# fridge-t10.net
KiCad netlist of a schematic drawn in EAGLE
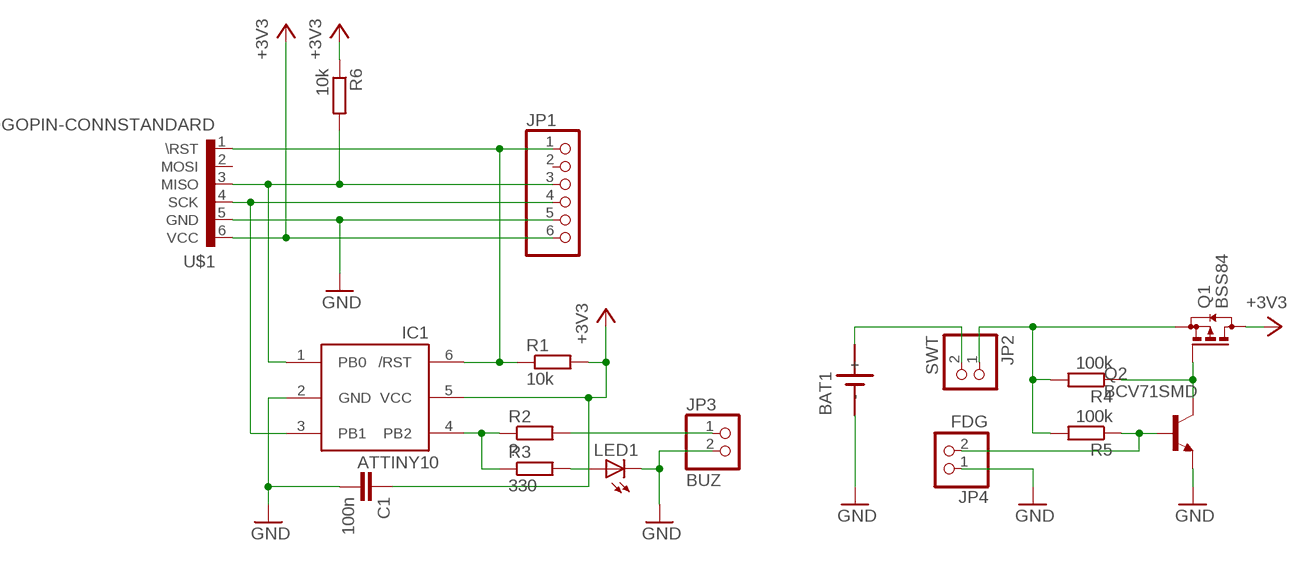
[diagram p0: schematic, sheet 1]

(export (version "E")
  (design (tool "Eeschema 10.0.6"))
  (components
    (comp (ref "BAT1")
      (value "SN2032")
      (footprint "eagle-import:SN2032")
      (libsource (lib "eagle-import") (part "SN2032"))
    )
    (comp (ref "C1")
      (value "100n")
      (footprint "eagle-import:C0805K")
      (libsource (lib "eagle-import") (part "C-EUC0805K"))
    )
    (comp (ref "IC1")
      (value "ATTINY10")
      (footprint "eagle-import:SOT23-6")
      (libsource (lib "eagle-import") (part "ATTINY10"))
    )
    (comp (ref "JP1")
      (value "PINHD-1X6")
      (footprint "eagle-import:1X06")
      (libsource (lib "eagle-import") (part "PINHD-1X6"))
    )
    (comp (ref "JP2")
      (value "SWT")
      (footprint "eagle-import:1X02")
      (libsource (lib "eagle-import") (part "PINHD-1X2"))
    )
    (comp (ref "JP3")
      (value "BUZ")
      (footprint "eagle-import:1X02")
      (libsource (lib "eagle-import") (part "PINHD-1X2"))
    )
    (comp (ref "JP4")
      (value "FDG")
      (footprint "eagle-import:1X02")
      (libsource (lib "eagle-import") (part "PINHD-1X2"))
    )
    (comp (ref "LED1")
      (value "LEDCHIPLED_0805")
      (footprint "eagle-import:CHIPLED_0805")
      (libsource (lib "eagle-import") (part "LEDCHIPLED_0805"))
    )
    (comp (ref "Q1")
      (value "BSS84")
      (footprint "eagle-import:SOT23")
      (libsource (lib "eagle-import") (part "BSS84"))
    )
    (comp (ref "Q2")
      (value "BCV71SMD")
      (footprint "eagle-import:SOT23-BEC")
      (libsource (lib "eagle-import") (part "BCV71SMD"))
    )
    (comp (ref "R1")
      (value "10k")
      (footprint "eagle-import:R0805")
      (libsource (lib "eagle-import") (part "R-EU_R0805"))
    )
    (comp (ref "R2")
      (value "?")
      (footprint "eagle-import:R0805")
      (libsource (lib "eagle-import") (part "R-EU_R0805"))
    )
    (comp (ref "R3")
      (value "330")
      (footprint "eagle-import:R0805")
      (libsource (lib "eagle-import") (part "R-EU_R0805"))
    )
    (comp (ref "R4")
      (value "100k")
      (footprint "eagle-import:R0805")
      (libsource (lib "eagle-import") (part "R-EU_R0805"))
    )
    (comp (ref "R5")
      (value "100k")
      (footprint "eagle-import:R0805")
      (libsource (lib "eagle-import") (part "R-EU_R0805"))
    )
    (comp (ref "R6")
      (value "10k")
      (footprint "eagle-import:R0805")
      (libsource (lib "eagle-import") (part "R-EU_R0805"))
    )
    (comp (ref "U$1")
      (value "POGOPIN-CONNSTANDARD")
      (footprint "eagle-import:POGOPROG-CONN")
      (libsource (lib "eagle-import") (part "POGOPIN-CONNSTANDARD"))
    )
  )
  (nets
    (net (code "1") (name "+3V3") (class "Default")
      (node (ref "C1") (pin "1") (pinfunction "1_1") (pintype "passive"))
      (node (ref "IC1") (pin "5") (pinfunction "VCC_5") (pintype "power_in"))
      (node (ref "JP1") (pin "6") (pinfunction "6_6") (pintype "passive"))
      (node (ref "Q1") (pin "3") (pinfunction "D_3") (pintype "passive"))
      (node (ref "R1") (pin "2") (pinfunction "2_2") (pintype "passive"))
      (node (ref "R6") (pin "1") (pinfunction "1_1") (pintype "passive"))
      (node (ref "U$1") (pin "6") (pinfunction "VCC_6") (pintype "bidirectional"))
    )
    (net (code "2") (name "GND") (class "Default")
      (node (ref "BAT1") (pin "-") (pinfunction "-_-") (pintype "passive"))
      (node (ref "C1") (pin "2") (pinfunction "2_2") (pintype "passive"))
      (node (ref "IC1") (pin "2") (pinfunction "GND_2") (pintype "power_in"))
      (node (ref "JP1") (pin "5") (pinfunction "5_5") (pintype "passive"))
      (node (ref "JP3") (pin "2") (pinfunction "2_2") (pintype "passive"))
      (node (ref "JP4") (pin "1") (pinfunction "1_1") (pintype "passive"))
      (node (ref "LED1") (pin "C") (pinfunction "C_C") (pintype "passive"))
      (node (ref "Q2") (pin "E") (pinfunction "E_E") (pintype "passive"))
      (node (ref "U$1") (pin "5") (pinfunction "GND_5") (pintype "bidirectional"))
    )
    (net (code "3") (name "Net-(BAT1-Pad+)") (class "Default")
      (node (ref "BAT1") (pin "+") (pinfunction "+_+") (pintype "passive"))
      (node (ref "JP2") (pin "2") (pinfunction "2_2") (pintype "passive"))
    )
    (net (code "4") (name "Net-(IC1-PB0)") (class "Default")
      (node (ref "IC1") (pin "1") (pinfunction "PB0_1") (pintype "bidirectional"))
      (node (ref "JP1") (pin "3") (pinfunction "3_3") (pintype "passive"))
      (node (ref "R6") (pin "2") (pinfunction "2_2") (pintype "passive"))
      (node (ref "U$1") (pin "3") (pinfunction "MISO_3") (pintype "bidirectional"))
    )
    (net (code "5") (name "Net-(IC1-PB1)") (class "Default")
      (node (ref "IC1") (pin "3") (pinfunction "PB1_3") (pintype "bidirectional"))
      (node (ref "JP1") (pin "4") (pinfunction "4_4") (pintype "passive"))
      (node (ref "U$1") (pin "4") (pinfunction "SCK_4") (pintype "bidirectional"))
    )
    (net (code "6") (name "Net-(IC1-PB2)") (class "Default")
      (node (ref "IC1") (pin "4") (pinfunction "PB2_4") (pintype "bidirectional"))
      (node (ref "R2") (pin "1") (pinfunction "1_1") (pintype "passive"))
      (node (ref "R3") (pin "1") (pinfunction "1_1") (pintype "passive"))
    )
    (net (code "7") (name "Net-(IC1-{slash}RST)") (class "Default")
      (node (ref "IC1") (pin "6") (pinfunction "/RST_6") (pintype "bidirectional"))
      (node (ref "JP1") (pin "1") (pinfunction "1_1") (pintype "passive"))
      (node (ref "R1") (pin "1") (pinfunction "1_1") (pintype "passive"))
      (node (ref "U$1") (pin "1") (pinfunction "\\RST_1") (pintype "bidirectional"))
    )
    (net (code "8") (name "Net-(JP3-Pad1)") (class "Default")
      (node (ref "JP3") (pin "1") (pinfunction "1_1") (pintype "passive"))
      (node (ref "R2") (pin "2") (pinfunction "2_2") (pintype "passive"))
    )
    (net (code "9") (name "Net-(JP4-Pad2)") (class "Default")
      (node (ref "JP4") (pin "2") (pinfunction "2_2") (pintype "passive"))
      (node (ref "Q2") (pin "B") (pinfunction "B_B") (pintype "passive"))
      (node (ref "R5") (pin "1") (pinfunction "1_1") (pintype "passive"))
    )
    (net (code "10") (name "Net-(LED1-PadA)") (class "Default")
      (node (ref "LED1") (pin "A") (pinfunction "A_A") (pintype "passive"))
      (node (ref "R3") (pin "2") (pinfunction "2_2") (pintype "passive"))
    )
    (net (code "11") (name "Net-(Q1-G)") (class "Default")
      (node (ref "Q1") (pin "1") (pinfunction "G_1") (pintype "passive"))
      (node (ref "Q2") (pin "C") (pinfunction "C_C") (pintype "passive"))
      (node (ref "R4") (pin "1") (pinfunction "1_1") (pintype "passive"))
    )
    (net (code "12") (name "Net-(Q1-S)") (class "Default")
      (node (ref "JP2") (pin "1") (pinfunction "1_1") (pintype "passive"))
      (node (ref "Q1") (pin "2") (pinfunction "S_2") (pintype "passive"))
      (node (ref "R4") (pin "2") (pinfunction "2_2") (pintype "passive"))
      (node (ref "R5") (pin "2") (pinfunction "2_2") (pintype "passive"))
    )
    (net (code "13") (name "unconnected-(JP1-Pad2)") (class "Default")
      (node (ref "JP1") (pin "2") (pinfunction "2_2") (pintype "passive"))
    )
    (net (code "14") (name "unconnected-(U$1-MOSI-Pad2)") (class "Default")
      (node (ref "U$1") (pin "2") (pinfunction "MOSI_2") (pintype "bidirectional"))
    )
  )
)
